# SQR_FG.net
KiCad netlist of a schematic drawn in EAGLE
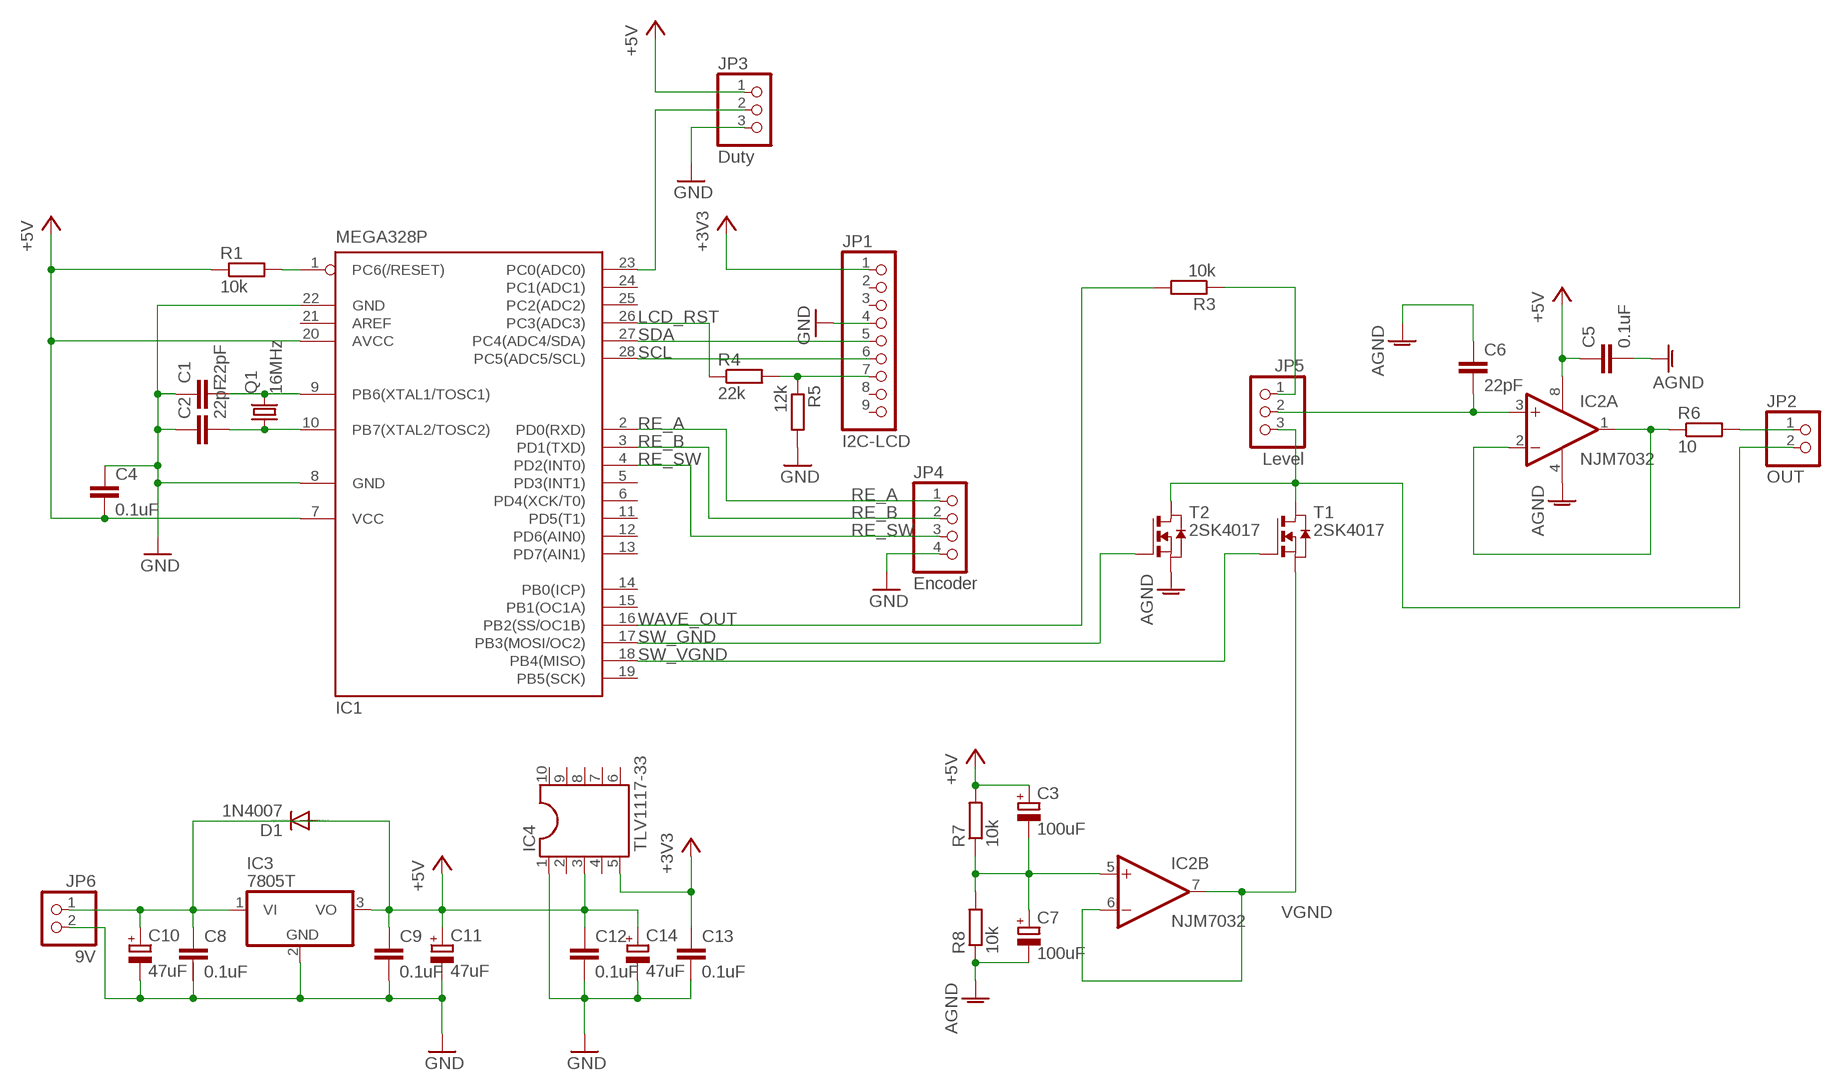
[diagram p0: schematic, sheet 1]

(export (version "E")
  (design (tool "Eeschema 10.0.6"))
  (components
    (comp (ref "C1")
      (value "22pF")
      (footprint "eagle-import:C025-024X044")
      (libsource (lib "eagle-import") (part "C-EU025-024X044"))
    )
    (comp (ref "C2")
      (value "22pF")
      (footprint "eagle-import:C025-024X044")
      (libsource (lib "eagle-import") (part "C-EU025-024X044"))
    )
    (comp (ref "C3")
      (value "100uF")
      (footprint "eagle-import:E2,5-5")
      (libsource (lib "eagle-import") (part "CPOL-EUE2.5-5"))
    )
    (comp (ref "C4")
      (value "0.1uF")
      (footprint "eagle-import:C025-024X044")
      (libsource (lib "eagle-import") (part "C-EU025-024X044"))
    )
    (comp (ref "C5")
      (value "0.1uF")
      (footprint "eagle-import:C025-024X044")
      (libsource (lib "eagle-import") (part "C-EU025-024X044"))
    )
    (comp (ref "C6")
      (value "22pF")
      (footprint "eagle-import:C025-024X044")
      (libsource (lib "eagle-import") (part "C-EU025-024X044"))
    )
    (comp (ref "C7")
      (value "100uF")
      (footprint "eagle-import:E2,5-5")
      (libsource (lib "eagle-import") (part "CPOL-EUE2.5-5"))
    )
    (comp (ref "C8")
      (value "0.1uF")
      (footprint "eagle-import:C025-024X044")
      (libsource (lib "eagle-import") (part "C-EU025-024X044"))
    )
    (comp (ref "C9")
      (value "0.1uF")
      (footprint "eagle-import:C025-024X044")
      (libsource (lib "eagle-import") (part "C-EU025-024X044"))
    )
    (comp (ref "C10")
      (value "47uF")
      (footprint "eagle-import:TT2D5L")
      (libsource (lib "eagle-import") (part "CPOL-EUTT2D5L"))
    )
    (comp (ref "C11")
      (value "47uF")
      (footprint "eagle-import:TT2D5L")
      (libsource (lib "eagle-import") (part "CPOL-EUTT2D5L"))
    )
    (comp (ref "C12")
      (value "0.1uF")
      (footprint "eagle-import:C025-024X044")
      (libsource (lib "eagle-import") (part "C-EU025-024X044"))
    )
    (comp (ref "C13")
      (value "0.1uF")
      (footprint "eagle-import:C025-024X044")
      (libsource (lib "eagle-import") (part "C-EU025-024X044"))
    )
    (comp (ref "C14")
      (value "47uF")
      (footprint "eagle-import:TT2D5L")
      (libsource (lib "eagle-import") (part "CPOL-EUTT2D5L"))
    )
    (comp (ref "D1")
      (value "1N4007")
      (footprint "eagle-import:DO41-10")
      (libsource (lib "eagle-import") (part "1N4004"))
    )
    (comp (ref "IC1")
      (value "MEGA328P")
      (footprint "eagle-import:DIL28-3")
      (libsource (lib "eagle-import") (part "MEGA8-P"))
    )
    (comp (ref "IC2")
      (value "NJM7032")
      (footprint "eagle-import:DIL08")
      (libsource (lib "eagle-import") (part "LM358N"))
    )
    (comp (ref "IC3")
      (value "7805T")
      (footprint "eagle-import:TO220H")
      (libsource (lib "eagle-import") (part "78T05"))
    )
    (comp (ref "IC4")
      (value "TLV1117-33")
      (footprint "eagle-import:DIL10")
      (libsource (lib "eagle-import") (part "DIL10"))
    )
    (comp (ref "JP1")
      (value "I2C-LCD")
      (footprint "eagle-import:1X09")
      (libsource (lib "eagle-import") (part "PINHD-1X9"))
    )
    (comp (ref "JP2")
      (value "OUT")
      (footprint "eagle-import:1X02")
      (libsource (lib "eagle-import") (part "PINHD-1X2"))
    )
    (comp (ref "JP3")
      (value "Duty")
      (footprint "eagle-import:1X03")
      (libsource (lib "eagle-import") (part "PINHD-1X3"))
    )
    (comp (ref "JP4")
      (value "Encoder")
      (footprint "eagle-import:1X04")
      (libsource (lib "eagle-import") (part "PINHD-1X4"))
    )
    (comp (ref "JP5")
      (value "Level")
      (footprint "eagle-import:1X03")
      (libsource (lib "eagle-import") (part "PINHD-1X3"))
    )
    (comp (ref "JP6")
      (value "9V")
      (footprint "eagle-import:1X02")
      (libsource (lib "eagle-import") (part "PINHD-1X2"))
    )
    (comp (ref "Q1")
      (value "16MHz")
      (footprint "eagle-import:HC49_S")
      (libsource (lib "eagle-import") (part "CRYSTALHC49S"))
    )
    (comp (ref "R1")
      (value "10k")
      (footprint "eagle-import:0207_7")
      (libsource (lib "eagle-import") (part "R-EU_0207/7"))
    )
    (comp (ref "R3")
      (value "10k")
      (footprint "eagle-import:0207_7")
      (libsource (lib "eagle-import") (part "R-EU_0207/7"))
    )
    (comp (ref "R4")
      (value "22k")
      (footprint "eagle-import:0207_7")
      (libsource (lib "eagle-import") (part "R-EU_0207/7"))
    )
    (comp (ref "R5")
      (value "12k")
      (footprint "eagle-import:0207_7")
      (libsource (lib "eagle-import") (part "R-EU_0207/7"))
    )
    (comp (ref "R6")
      (value "10")
      (footprint "eagle-import:0207_7")
      (libsource (lib "eagle-import") (part "R-EU_0207/7"))
    )
    (comp (ref "R7")
      (value "10k")
      (footprint "eagle-import:0207_7")
      (libsource (lib "eagle-import") (part "R-EU_0207/7"))
    )
    (comp (ref "R8")
      (value "10k")
      (footprint "eagle-import:0207_7")
      (libsource (lib "eagle-import") (part "R-EU_0207/7"))
    )
    (comp (ref "T1")
      (value "2SK4017")
      (footprint "eagle-import:E3LINE")
      (libsource (lib "eagle-import") (part "NMOSE3L"))
    )
    (comp (ref "T2")
      (value "2SK4017")
      (footprint "eagle-import:E3LINE")
      (libsource (lib "eagle-import") (part "NMOSE3L"))
    )
  )
  (nets
    (net (code "1") (name "+3V3") (class "Default")
      (node (ref "C13") (pin "1") (pinfunction "1_1") (pintype "passive"))
      (node (ref "IC4") (pin "5") (pinfunction "5_5") (pintype "passive"))
      (node (ref "JP1") (pin "1") (pinfunction "1_1") (pintype "passive"))
    )
    (net (code "2") (name "+5V") (class "Default")
      (node (ref "C10") (pin "+") (pinfunction "+_+") (pintype "passive"))
      (node (ref "C11") (pin "+") (pinfunction "+_+") (pintype "passive"))
      (node (ref "C12") (pin "1") (pinfunction "1_1") (pintype "passive"))
      (node (ref "C14") (pin "+") (pinfunction "+_+") (pintype "passive"))
      (node (ref "C3") (pin "+") (pinfunction "+_+") (pintype "passive"))
      (node (ref "C4") (pin "2") (pinfunction "2_2") (pintype "passive"))
      (node (ref "C5") (pin "1") (pinfunction "1_1") (pintype "passive"))
      (node (ref "C8") (pin "1") (pinfunction "1_1") (pintype "passive"))
      (node (ref "C9") (pin "1") (pinfunction "1_1") (pintype "passive"))
      (node (ref "IC1") (pin "20") (pinfunction "AVCC_20") (pintype "power_in"))
      (node (ref "IC1") (pin "7") (pinfunction "VCC_7") (pintype "power_in"))
      (node (ref "IC2") (pin "8") (pinfunction "V+_8") (pintype "power_in"))
      (node (ref "IC3") (pin "1") (pinfunction "VI_1") (pintype "input"))
      (node (ref "IC3") (pin "3") (pinfunction "VO_3") (pintype "passive"))
      (node (ref "IC4") (pin "3") (pinfunction "3_3") (pintype "passive"))
      (node (ref "JP3") (pin "1") (pinfunction "1_1") (pintype "passive"))
      (node (ref "JP6") (pin "1") (pinfunction "1_1") (pintype "passive"))
      (node (ref "R1") (pin "1") (pinfunction "1_1") (pintype "passive"))
      (node (ref "R7") (pin "2") (pinfunction "2_2") (pintype "passive"))
    )
    (net (code "3") (name "/LCD_RST") (class "Default")
      (node (ref "IC1") (pin "26") (pinfunction "PC3(ADC3)_26") (pintype "bidirectional"))
      (node (ref "R4") (pin "1") (pinfunction "1_1") (pintype "passive"))
    )
    (net (code "4") (name "/RE_A") (class "Default")
      (node (ref "IC1") (pin "2") (pinfunction "PD0(RXD)_2") (pintype "bidirectional"))
      (node (ref "JP4") (pin "1") (pinfunction "1_1") (pintype "passive"))
    )
    (net (code "5") (name "/RE_B") (class "Default")
      (node (ref "IC1") (pin "3") (pinfunction "PD1(TXD)_3") (pintype "bidirectional"))
      (node (ref "JP4") (pin "2") (pinfunction "2_2") (pintype "passive"))
    )
    (net (code "6") (name "/RE_SW") (class "Default")
      (node (ref "IC1") (pin "4") (pinfunction "PD2(INT0)_4") (pintype "bidirectional"))
      (node (ref "JP4") (pin "3") (pinfunction "3_3") (pintype "passive"))
    )
    (net (code "7") (name "/SCL") (class "Default")
      (node (ref "IC1") (pin "28") (pinfunction "PC5(ADC5/SCL)_28") (pintype "bidirectional"))
      (node (ref "JP1") (pin "6") (pinfunction "6_6") (pintype "passive"))
    )
    (net (code "8") (name "/SDA") (class "Default")
      (node (ref "IC1") (pin "27") (pinfunction "PC4(ADC4/SDA)_27") (pintype "bidirectional"))
      (node (ref "JP1") (pin "5") (pinfunction "5_5") (pintype "passive"))
    )
    (net (code "9") (name "/SW_GND") (class "Default")
      (node (ref "IC1") (pin "17") (pinfunction "PB3(MOSI/OC2)_17") (pintype "bidirectional"))
      (node (ref "T2") (pin "2") (pinfunction "G_2") (pintype "passive"))
    )
    (net (code "10") (name "/SW_VGND") (class "Default")
      (node (ref "IC1") (pin "18") (pinfunction "PB4(MISO)_18") (pintype "bidirectional"))
      (node (ref "T1") (pin "2") (pinfunction "G_2") (pintype "passive"))
    )
    (net (code "11") (name "/VGND") (class "Default")
      (node (ref "IC2") (pin "6") (pinfunction "-IN_6") (pintype "input"))
      (node (ref "IC2") (pin "7") (pinfunction "OUT_7") (pintype "output"))
      (node (ref "T1") (pin "3") (pinfunction "S_3") (pintype "passive"))
    )
    (net (code "12") (name "/WAVE_OUT") (class "Default")
      (node (ref "IC1") (pin "16") (pinfunction "PB2(SS/OC1B)_16") (pintype "bidirectional"))
      (node (ref "R3") (pin "2") (pinfunction "2_2") (pintype "passive"))
    )
    (net (code "13") (name "AGND") (class "Default")
      (node (ref "C5") (pin "2") (pinfunction "2_2") (pintype "passive"))
      (node (ref "C6") (pin "1") (pinfunction "1_1") (pintype "passive"))
      (node (ref "C7") (pin "-") (pinfunction "-_-") (pintype "passive"))
      (node (ref "IC2") (pin "4") (pinfunction "V-_4") (pintype "power_in"))
      (node (ref "R8") (pin "1") (pinfunction "1_1") (pintype "passive"))
      (node (ref "T2") (pin "3") (pinfunction "S_3") (pintype "passive"))
    )
    (net (code "14") (name "GND") (class "Default")
      (node (ref "C1") (pin "1") (pinfunction "1_1") (pintype "passive"))
      (node (ref "C10") (pin "-") (pinfunction "-_-") (pintype "passive"))
      (node (ref "C11") (pin "-") (pinfunction "-_-") (pintype "passive"))
      (node (ref "C12") (pin "2") (pinfunction "2_2") (pintype "passive"))
      (node (ref "C13") (pin "2") (pinfunction "2_2") (pintype "passive"))
      (node (ref "C14") (pin "-") (pinfunction "-_-") (pintype "passive"))
      (node (ref "C2") (pin "1") (pinfunction "1_1") (pintype "passive"))
      (node (ref "C4") (pin "1") (pinfunction "1_1") (pintype "passive"))
      (node (ref "C8") (pin "2") (pinfunction "2_2") (pintype "passive"))
      (node (ref "C9") (pin "2") (pinfunction "2_2") (pintype "passive"))
      (node (ref "IC1") (pin "22") (pinfunction "GND_22") (pintype "power_in"))
      (node (ref "IC1") (pin "8") (pinfunction "GND_8") (pintype "power_in"))
      (node (ref "IC3") (pin "2") (pinfunction "GND_2") (pintype "passive"))
      (node (ref "IC4") (pin "1") (pinfunction "1_1") (pintype "passive"))
      (node (ref "JP1") (pin "4") (pinfunction "4_4") (pintype "passive"))
      (node (ref "JP3") (pin "3") (pinfunction "3_3") (pintype "passive"))
      (node (ref "JP4") (pin "4") (pinfunction "4_4") (pintype "passive"))
      (node (ref "JP6") (pin "2") (pinfunction "2_2") (pintype "passive"))
      (node (ref "R5") (pin "2") (pinfunction "2_2") (pintype "passive"))
    )
    (net (code "15") (name "Net-(IC1-PB6(XTAL1{slash}TOSC1))") (class "Default")
      (node (ref "C1") (pin "2") (pinfunction "2_2") (pintype "passive"))
      (node (ref "IC1") (pin "9") (pinfunction "PB6(XTAL1/TOSC1)_9") (pintype "bidirectional"))
      (node (ref "Q1") (pin "2") (pinfunction "2_2") (pintype "passive"))
    )
    (net (code "16") (name "Net-(IC1-PB7(XTAL2{slash}TOSC2))") (class "Default")
      (node (ref "C2") (pin "2") (pinfunction "2_2") (pintype "passive"))
      (node (ref "IC1") (pin "10") (pinfunction "PB7(XTAL2/TOSC2)_10") (pintype "bidirectional"))
      (node (ref "Q1") (pin "1") (pinfunction "1_1") (pintype "passive"))
    )
    (net (code "17") (name "Net-(IC1-PC0(ADC0))") (class "Default")
      (node (ref "IC1") (pin "23") (pinfunction "PC0(ADC0)_23") (pintype "bidirectional"))
      (node (ref "JP3") (pin "2") (pinfunction "2_2") (pintype "passive"))
    )
    (net (code "18") (name "Net-(IC1-PC6({slash}RESET))") (class "Default")
      (node (ref "IC1") (pin "1") (pinfunction "PC6(/RESET)_1") (pintype "bidirectional"))
      (node (ref "R1") (pin "2") (pinfunction "2_2") (pintype "passive"))
    )
    (net (code "19") (name "Net-(IC2A-+IN)") (class "Default")
      (node (ref "C6") (pin "2") (pinfunction "2_2") (pintype "passive"))
      (node (ref "IC2") (pin "3") (pinfunction "+IN_3") (pintype "input"))
      (node (ref "JP5") (pin "2") (pinfunction "2_2") (pintype "passive"))
    )
    (net (code "20") (name "Net-(IC2A--IN)") (class "Default")
      (node (ref "IC2") (pin "1") (pinfunction "OUT_1") (pintype "output"))
      (node (ref "IC2") (pin "2") (pinfunction "-IN_2") (pintype "input"))
      (node (ref "R6") (pin "1") (pinfunction "1_1") (pintype "passive"))
    )
    (net (code "21") (name "Net-(IC2B-+IN)") (class "Default")
      (node (ref "C3") (pin "-") (pinfunction "-_-") (pintype "passive"))
      (node (ref "C7") (pin "+") (pinfunction "+_+") (pintype "passive"))
      (node (ref "IC2") (pin "5") (pinfunction "+IN_5") (pintype "input"))
      (node (ref "R7") (pin "1") (pinfunction "1_1") (pintype "passive"))
      (node (ref "R8") (pin "2") (pinfunction "2_2") (pintype "passive"))
    )
    (net (code "22") (name "Net-(JP1-Pad7)") (class "Default")
      (node (ref "JP1") (pin "7") (pinfunction "7_7") (pintype "passive"))
      (node (ref "R4") (pin "2") (pinfunction "2_2") (pintype "passive"))
      (node (ref "R5") (pin "1") (pinfunction "1_1") (pintype "passive"))
    )
    (net (code "23") (name "Net-(JP2-Pad1)") (class "Default")
      (node (ref "JP2") (pin "1") (pinfunction "1_1") (pintype "passive"))
      (node (ref "R6") (pin "2") (pinfunction "2_2") (pintype "passive"))
    )
    (net (code "24") (name "Net-(JP5-Pad1)") (class "Default")
      (node (ref "JP5") (pin "1") (pinfunction "1_1") (pintype "passive"))
      (node (ref "R3") (pin "1") (pinfunction "1_1") (pintype "passive"))
    )
    (net (code "25") (name "Net-(T1-D)") (class "Default")
      (node (ref "JP2") (pin "2") (pinfunction "2_2") (pintype "passive"))
      (node (ref "JP5") (pin "3") (pinfunction "3_3") (pintype "passive"))
      (node (ref "T1") (pin "1") (pinfunction "D_1") (pintype "passive"))
      (node (ref "T2") (pin "1") (pinfunction "D_1") (pintype "passive"))
    )
    (net (code "26") (name "unconnected-(D1-PadA)") (class "Default")
      (node (ref "D1") (pin "A") (pinfunction "A_A") (pintype "passive"))
    )
    (net (code "27") (name "unconnected-(D1-PadC)") (class "Default")
      (node (ref "D1") (pin "C") (pinfunction "C_C") (pintype "passive"))
    )
    (net (code "28") (name "unconnected-(IC1-AREF-Pad21)") (class "Default")
      (node (ref "IC1") (pin "21") (pinfunction "AREF_21") (pintype "passive"))
    )
    (net (code "29") (name "unconnected-(IC1-PB0(ICP)-Pad14)") (class "Default")
      (node (ref "IC1") (pin "14") (pinfunction "PB0(ICP)_14") (pintype "bidirectional"))
    )
    (net (code "30") (name "unconnected-(IC1-PB1(OC1A)-Pad15)") (class "Default")
      (node (ref "IC1") (pin "15") (pinfunction "PB1(OC1A)_15") (pintype "bidirectional"))
    )
    (net (code "31") (name "unconnected-(IC1-PB5(SCK)-Pad19)") (class "Default")
      (node (ref "IC1") (pin "19") (pinfunction "PB5(SCK)_19") (pintype "bidirectional"))
    )
    (net (code "32") (name "unconnected-(IC1-PC1(ADC1)-Pad24)") (class "Default")
      (node (ref "IC1") (pin "24") (pinfunction "PC1(ADC1)_24") (pintype "bidirectional"))
    )
    (net (code "33") (name "unconnected-(IC1-PC2(ADC2)-Pad25)") (class "Default")
      (node (ref "IC1") (pin "25") (pinfunction "PC2(ADC2)_25") (pintype "bidirectional"))
    )
    (net (code "34") (name "unconnected-(IC1-PD3(INT1)-Pad5)") (class "Default")
      (node (ref "IC1") (pin "5") (pinfunction "PD3(INT1)_5") (pintype "bidirectional"))
    )
    (net (code "35") (name "unconnected-(IC1-PD4(XCK{slash}T0)-Pad6)") (class "Default")
      (node (ref "IC1") (pin "6") (pinfunction "PD4(XCK/T0)_6") (pintype "bidirectional"))
    )
    (net (code "36") (name "unconnected-(IC1-PD5(T1)-Pad11)") (class "Default")
      (node (ref "IC1") (pin "11") (pinfunction "PD5(T1)_11") (pintype "bidirectional"))
    )
    (net (code "37") (name "unconnected-(IC1-PD6(AIN0)-Pad12)") (class "Default")
      (node (ref "IC1") (pin "12") (pinfunction "PD6(AIN0)_12") (pintype "bidirectional"))
    )
    (net (code "38") (name "unconnected-(IC1-PD7(AIN1)-Pad13)") (class "Default")
      (node (ref "IC1") (pin "13") (pinfunction "PD7(AIN1)_13") (pintype "bidirectional"))
    )
    (net (code "39") (name "unconnected-(IC4-Pad2)") (class "Default")
      (node (ref "IC4") (pin "2") (pinfunction "2_2") (pintype "passive"))
    )
    (net (code "40") (name "unconnected-(IC4-Pad4)") (class "Default")
      (node (ref "IC4") (pin "4") (pinfunction "4_4") (pintype "passive"))
    )
    (net (code "41") (name "unconnected-(IC4-Pad6)") (class "Default")
      (node (ref "IC4") (pin "6") (pinfunction "6_6") (pintype "passive"))
    )
    (net (code "42") (name "unconnected-(IC4-Pad7)") (class "Default")
      (node (ref "IC4") (pin "7") (pinfunction "7_7") (pintype "passive"))
    )
    (net (code "43") (name "unconnected-(IC4-Pad8)") (class "Default")
      (node (ref "IC4") (pin "8") (pinfunction "8_8") (pintype "passive"))
    )
    (net (code "44") (name "unconnected-(IC4-Pad9)") (class "Default")
      (node (ref "IC4") (pin "9") (pinfunction "9_9") (pintype "passive"))
    )
    (net (code "45") (name "unconnected-(IC4-Pad10)") (class "Default")
      (node (ref "IC4") (pin "10") (pinfunction "10_10") (pintype "passive"))
    )
    (net (code "46") (name "unconnected-(JP1-Pad2)") (class "Default")
      (node (ref "JP1") (pin "2") (pinfunction "2_2") (pintype "passive"))
    )
    (net (code "47") (name "unconnected-(JP1-Pad3)") (class "Default")
      (node (ref "JP1") (pin "3") (pinfunction "3_3") (pintype "passive"))
    )
    (net (code "48") (name "unconnected-(JP1-Pad8)") (class "Default")
      (node (ref "JP1") (pin "8") (pinfunction "8_8") (pintype "passive"))
    )
    (net (code "49") (name "unconnected-(JP1-Pad9)") (class "Default")
      (node (ref "JP1") (pin "9") (pinfunction "9_9") (pintype "passive"))
    )
  )
)
